# USB_OTG.net
KiCad netlist of a schematic drawn in Altium Designer
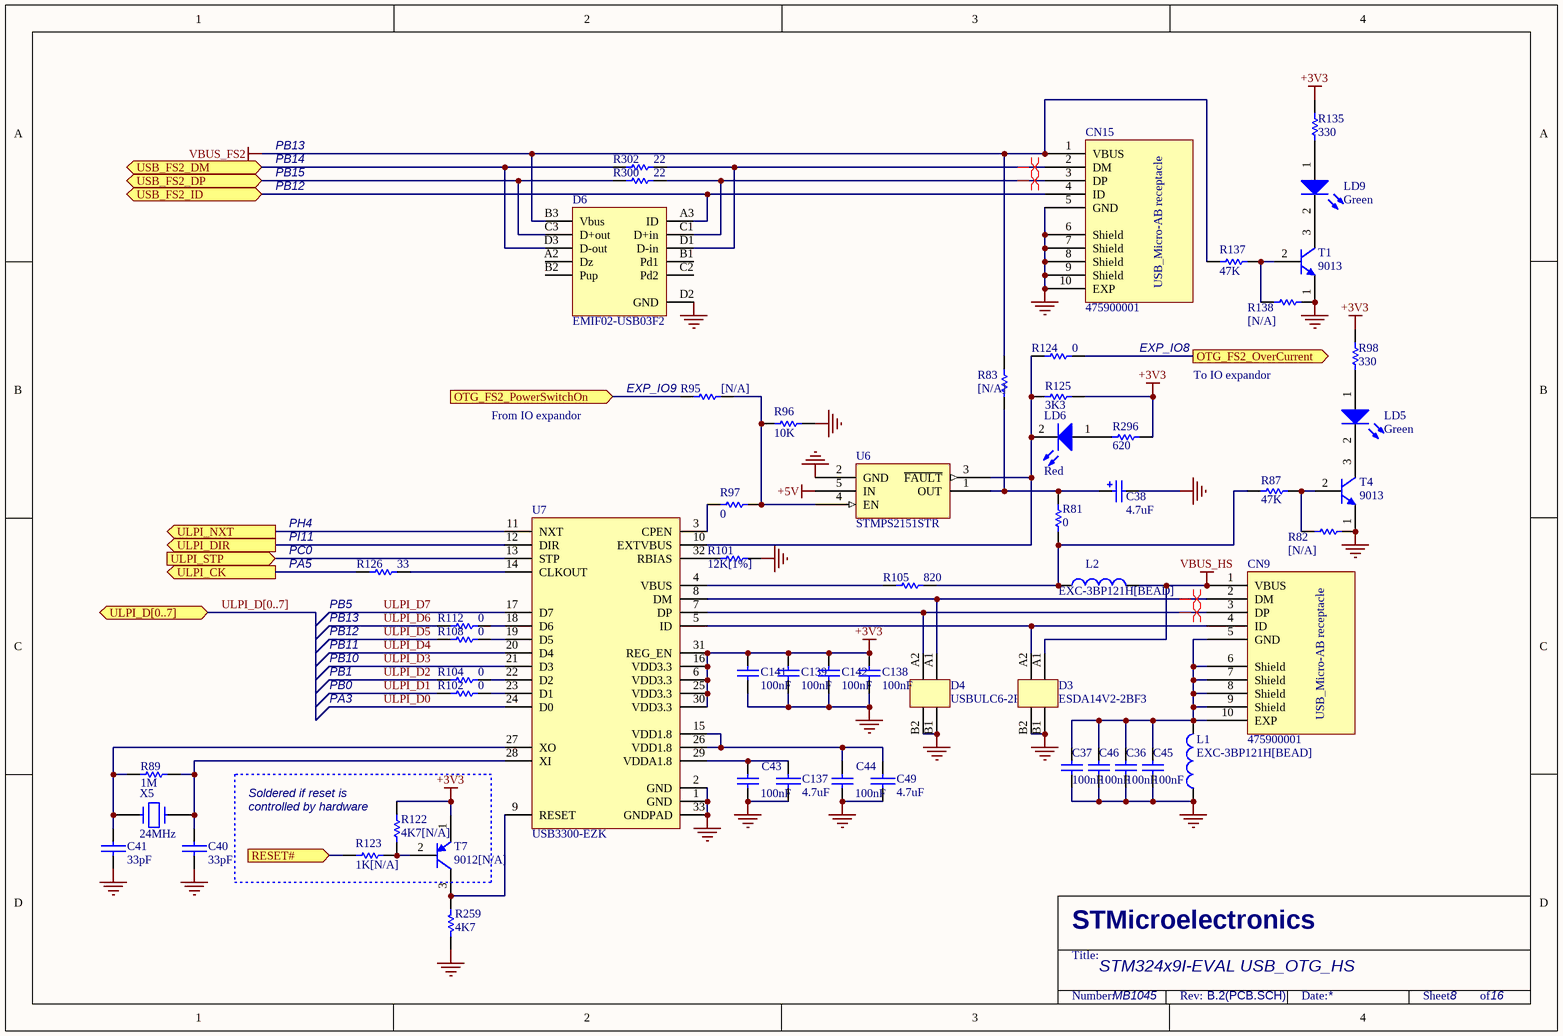
[diagram p0: USB_OTG.SchDoc]

(export (version "E")
  (design (tool "Eeschema 10.0.6"))
  (components
    (comp (ref "C36")
      (value "100nF")
      (footprint "0603C")
      (description "Capacitor")
      (fields (field (name "PUBLISHER") "Altium Limited"))
      (libsource (lib "Miscellaneous Devices") (part "Cap"))
    )
    (comp (ref "C37")
      (value "100nF")
      (footprint "0603C")
      (description "Capacitor")
      (fields (field (name "PUBLISHER") "Altium Limited"))
      (libsource (lib "Miscellaneous Devices") (part "Cap"))
    )
    (comp (ref "C38")
      (value "4.7uF")
      (footprint "TAN-A")
      (description "Polarized Capacitor (Radial)")
      (fields (field (name "PUBLISHER") "Altium Limited"))
      (libsource (lib "Miscellaneous Devices") (part "Cap Pol1"))
    )
    (comp (ref "C40")
      (value "33pF")
      (footprint "0603C")
      (description "Capacitor")
      (libsource (lib "") (part "CAP_1"))
    )
    (comp (ref "C41")
      (value "33pF")
      (footprint "0603C")
      (description "Capacitor")
      (libsource (lib "") (part "CAP_1"))
    )
    (comp (ref "C43")
      (value "100nF")
      (footprint "0603C")
      (description "Capacitor")
      (fields (field (name "PUBLISHER") "Altium Limited"))
      (libsource (lib "Miscellaneous Devices") (part "Cap"))
    )
    (comp (ref "C44")
      (value "100nF")
      (footprint "0603C")
      (description "Capacitor")
      (fields (field (name "PUBLISHER") "Altium Limited"))
      (libsource (lib "Miscellaneous Devices") (part "Cap"))
    )
    (comp (ref "C45")
      (value "100nF")
      (footprint "0603C")
      (description "Capacitor")
      (fields (field (name "PUBLISHER") "Altium Limited"))
      (libsource (lib "Miscellaneous Devices") (part "Cap"))
    )
    (comp (ref "C46")
      (value "100nF")
      (footprint "0603C")
      (description "Capacitor")
      (fields (field (name "PUBLISHER") "Altium Limited"))
      (libsource (lib "Miscellaneous Devices") (part "Cap"))
    )
    (comp (ref "C49")
      (value "4.7uF")
      (footprint "TAN-A")
      (description "Capacitor")
      (libsource (lib "*") (part "CAP"))
    )
    (comp (ref "C137")
      (value "4.7uF")
      (footprint "TAN-A")
      (description "Capacitor")
      (libsource (lib "*") (part "CAP"))
    )
    (comp (ref "C138")
      (value "100nF")
      (footprint "0603C")
      (description "Capacitor")
      (fields (field (name "PUBLISHER") "Altium Limited"))
      (libsource (lib "Miscellaneous Devices") (part "Cap"))
    )
    (comp (ref "C139")
      (value "100nF")
      (footprint "0603C")
      (description "Capacitor")
      (fields (field (name "PUBLISHER") "Altium Limited"))
      (libsource (lib "Miscellaneous Devices") (part "Cap"))
    )
    (comp (ref "C141")
      (value "100nF")
      (footprint "0603C")
      (description "Capacitor")
      (fields (field (name "PUBLISHER") "Altium Limited"))
      (libsource (lib "Miscellaneous Devices") (part "Cap"))
    )
    (comp (ref "C142")
      (value "100nF")
      (footprint "0603C")
      (description "Capacitor")
      (fields (field (name "PUBLISHER") "Altium Limited"))
      (libsource (lib "Miscellaneous Devices") (part "Cap"))
    )
    (comp (ref "CN9")
      (value "475900001")
      (footprint "MOLEX_47590001")
      (libsource (lib "mb1045") (part "475900001"))
    )
    (comp (ref "CN15")
      (value "475900001")
      (footprint "MOLEX_47590001")
      (libsource (lib "mb1045") (part "475900001"))
    )
    (comp (ref "D3")
      (value "ESDA14V2-2BF3")
      (footprint "BGA4_0R4_0R8X0R8")
      (libsource (lib "MB786") (part "ESDA14V2-2BF3"))
    )
    (comp (ref "D4")
      (value "USBULC6-2F3")
      (footprint "BGA4_0R4_1X1")
      (libsource (lib "MB786") (part "USBULC6-2F3"))
    )
    (comp (ref "D6")
      (value "EMIF02-USB03F2")
      (footprint "BGA11_0R5_1R57X2R07")
      (libsource (lib "mb1045") (part "EMIF02-USB03F2"))
    )
    (comp (ref "L1")
      (value "EXC-3BP121H[BEAD]")
      (footprint "0603L")
      (description "Inductor")
      (fields (field (name "PUBLISHER") "Altium Limited"))
      (libsource (lib "Miscellaneous Devices") (part "Inductor"))
    )
    (comp (ref "L2")
      (value "EXC-3BP121H[BEAD]")
      (footprint "0603L")
      (description "Inductor")
      (fields (field (name "PUBLISHER") "Altium Limited"))
      (libsource (lib "Miscellaneous Devices") (part "Inductor"))
    )
    (comp (ref "LD5")
      (value "Green")
      (footprint "0603D")
      (description "Typical RED, GREEN, YELLOW, AMBER GaAs LED")
      (fields (field (name "PUBLISHER") "Altium Limited"))
      (libsource (lib "Miscellaneous Devices") (part "LED2"))
    )
    (comp (ref "LD6")
      (value "Red")
      (footprint "0603D")
      (description "Typical RED, GREEN, YELLOW, AMBER GaAs LED")
      (fields (field (name "PUBLISHER") "Altium Limited"))
      (libsource (lib "Miscellaneous Devices") (part "LED2"))
    )
    (comp (ref "LD9")
      (value "Green")
      (footprint "0603D")
      (description "Typical RED, GREEN, YELLOW, AMBER GaAs LED")
      (fields (field (name "PUBLISHER") "Altium Limited"))
      (libsource (lib "Miscellaneous Devices") (part "LED2"))
    )
    (comp (ref "R81")
      (value "0")
      (footprint "0603R")
      (description "Resistor")
      (fields (field (name "PUBLISHER") "Altium Limited"))
      (libsource (lib "Miscellaneous Devices") (part "Res1"))
    )
    (comp (ref "R82")
      (value "[N/A]")
      (footprint "0603R")
      (description "Resistor")
      (fields (field (name "PUBLISHER") "Altium Limited"))
      (libsource (lib "Miscellaneous Devices") (part "res1"))
    )
    (comp (ref "R83")
      (value "[N/A]")
      (footprint "0603R")
      (description "Resistor")
      (fields (field (name "PUBLISHER") "Altium Limited"))
      (libsource (lib "Miscellaneous Devices") (part "Res1"))
    )
    (comp (ref "R87")
      (value "47K")
      (footprint "0603R")
      (description "Resistor")
      (fields (field (name "PUBLISHER") "Altium Limited"))
      (libsource (lib "Miscellaneous Devices") (part "res1"))
    )
    (comp (ref "R89")
      (value "1M")
      (footprint "0603R")
      (description "Resistor")
      (fields (field (name "PUBLISHER") "Altium Limited"))
      (libsource (lib "Miscellaneous Devices") (part "Res1"))
    )
    (comp (ref "R95")
      (value "[N/A]")
      (footprint "0603R")
      (description "Resistor")
      (fields (field (name "PUBLISHER") "Altium Limited"))
      (libsource (lib "Miscellaneous Devices") (part "Res1"))
    )
    (comp (ref "R96")
      (value "10K")
      (footprint "0603R")
      (description "Resistor")
      (fields (field (name "PUBLISHER") "Altium Limited"))
      (libsource (lib "Miscellaneous Devices") (part "res1"))
    )
    (comp (ref "R97")
      (value "0")
      (footprint "0603R")
      (description "Resistor")
      (fields (field (name "PUBLISHER") "Altium Limited"))
      (libsource (lib "Miscellaneous Devices") (part "Res1"))
    )
    (comp (ref "R98")
      (value "330")
      (footprint "0603R")
      (description "Resistor")
      (fields (field (name "PUBLISHER") "Altium Limited"))
      (libsource (lib "Miscellaneous Devices") (part "res1"))
    )
    (comp (ref "R101")
      (value "12K[1%]")
      (footprint "0603R")
      (description "Resistor")
      (fields (field (name "PUBLISHER") "Altium Limited"))
      (libsource (lib "Miscellaneous Devices") (part "Res1"))
    )
    (comp (ref "R102")
      (value "0")
      (footprint "0603R")
      (description "Resistor")
      (fields (field (name "PUBLISHER") "Altium Limited"))
      (libsource (lib "Miscellaneous Devices") (part "Res1"))
    )
    (comp (ref "R104")
      (value "0")
      (footprint "0603R")
      (description "Resistor")
      (fields (field (name "PUBLISHER") "Altium Limited"))
      (libsource (lib "Miscellaneous Devices") (part "Res1"))
    )
    (comp (ref "R105")
      (value "820")
      (footprint "0603R")
      (description "Resistor")
      (fields (field (name "PUBLISHER") "Altium Limited"))
      (libsource (lib "Miscellaneous Devices") (part "res1"))
    )
    (comp (ref "R108")
      (value "0")
      (footprint "0603R")
      (description "Resistor")
      (fields (field (name "PUBLISHER") "Altium Limited"))
      (libsource (lib "Miscellaneous Devices") (part "Res1"))
    )
    (comp (ref "R112")
      (value "0")
      (footprint "0603R")
      (description "Resistor")
      (fields (field (name "PUBLISHER") "Altium Limited"))
      (libsource (lib "Miscellaneous Devices") (part "Res1"))
    )
    (comp (ref "R122")
      (value "4K7[N/A]")
      (footprint "0603R")
      (description "Resistor")
      (fields (field (name "PUBLISHER") "Altium Limited"))
      (libsource (lib "*") (part "Res1"))
    )
    (comp (ref "R123")
      (value "1K[N/A]")
      (footprint "0603R")
      (description "Resistor")
      (fields (field (name "PUBLISHER") "Altium Limited"))
      (libsource (lib "Miscellaneous Devices") (part "Res1"))
    )
    (comp (ref "R124")
      (value "0")
      (footprint "0603R")
      (description "Resistor")
      (fields (field (name "PUBLISHER") "Altium Limited"))
      (libsource (lib "Miscellaneous Devices") (part "Res1"))
    )
    (comp (ref "R125")
      (value "3K3")
      (footprint "0603R")
      (description "Resistor")
      (fields (field (name "PUBLISHER") "Altium Limited"))
      (libsource (lib "Miscellaneous Devices") (part "res1"))
    )
    (comp (ref "R126")
      (value "33")
      (footprint "0603R")
      (description "Resistor")
      (fields (field (name "PUBLISHER") "Altium Limited"))
      (libsource (lib "Miscellaneous Devices") (part "Res1"))
    )
    (comp (ref "R135")
      (value "330")
      (footprint "0603R")
      (description "Resistor")
      (fields (field (name "PUBLISHER") "Altium Limited"))
      (libsource (lib "Miscellaneous Devices") (part "res1"))
    )
    (comp (ref "R137")
      (value "47K")
      (footprint "0603R")
      (description "Resistor")
      (fields (field (name "PUBLISHER") "Altium Limited"))
      (libsource (lib "Miscellaneous Devices") (part "res1"))
    )
    (comp (ref "R138")
      (value "[N/A]")
      (footprint "0603R")
      (description "Resistor")
      (fields (field (name "PUBLISHER") "Altium Limited"))
      (libsource (lib "Miscellaneous Devices") (part "res1"))
    )
    (comp (ref "R259")
      (value "4K7")
      (footprint "0603R")
      (description "Resistor")
      (fields (field (name "PUBLISHER") "Altium Limited"))
      (libsource (lib "*") (part "Res1"))
    )
    (comp (ref "R296")
      (value "620")
      (footprint "0603R")
      (description "Resistor")
      (fields (field (name "PUBLISHER") "Altium Limited"))
      (libsource (lib "Miscellaneous Devices") (part "Res1"))
    )
    (comp (ref "R300")
      (value "22")
      (footprint "0603R")
      (description "Resistor")
      (fields (field (name "PUBLISHER") "Altium Limited"))
      (libsource (lib "Miscellaneous Devices") (part "Res1"))
    )
    (comp (ref "R302")
      (value "22")
      (footprint "0603R")
      (description "Resistor")
      (fields (field (name "PUBLISHER") "Altium Limited"))
      (libsource (lib "Miscellaneous Devices") (part "Res1"))
    )
    (comp (ref "T1")
      (value "9013")
      (footprint "SOT23-213")
      (description "NPN Bipolar Transistor")
      (fields (field (name "PUBLISHER") "Altium Limited"))
      (libsource (lib "mb1045") (part "NPN"))
    )
    (comp (ref "T4")
      (value "9013")
      (footprint "SOT23-213")
      (description "NPN Bipolar Transistor")
      (fields (field (name "PUBLISHER") "Altium Limited"))
      (libsource (lib "mb1045") (part "NPN"))
    )
    (comp (ref "T7")
      (value "9012[N/A]")
      (footprint "SOT23-213")
      (description "PNP Bipolar Transistor")
      (fields (field (name "PUBLISHER") "Altium Limited"))
      (libsource (lib "Miscellaneous Devices") (part "PNP"))
    )
    (comp (ref "U6")
      (value "STMPS2151STR")
      (footprint "SOT23-5")
      (libsource (lib "mb1045") (part "STMPS2141STR"))
    )
    (comp (ref "U7")
      (value "USB3300-EZK")
      (footprint "QFN32_0R5_5X5")
      (libsource (lib "MB1000_1") (part "USB3300-EZK"))
    )
    (comp (ref "X5")
      (value "24MHz")
      (footprint "XTAL1")
      (description "Crystal")
      (libsource (lib "*") (part "CRYSTAL"))
    )
  )
  (nets
    (net (code "1") (name "+3V3") (class "Default")
      (node (ref "C138") (pin "1") (pinfunction "1_1") (pintype "passive"))
      (node (ref "C139") (pin "1") (pinfunction "1_1") (pintype "passive"))
      (node (ref "C141") (pin "1") (pinfunction "1_1") (pintype "passive"))
      (node (ref "C142") (pin "1") (pinfunction "1_1") (pintype "passive"))
      (node (ref "R122") (pin "1") (pinfunction "1_1") (pintype "passive"))
      (node (ref "R125") (pin "1") (pinfunction "1_1") (pintype "passive"))
      (node (ref "R135") (pin "2") (pinfunction "2_2") (pintype "passive"))
      (node (ref "R296") (pin "2") (pinfunction "2_2") (pintype "passive"))
      (node (ref "R98") (pin "2") (pinfunction "2_2") (pintype "passive"))
      (node (ref "T7") (pin "1") (pinfunction "E_1") (pintype "passive"))
      (node (ref "U7") (pin "16") (pinfunction "VDD3.3_16") (pintype "passive"))
      (node (ref "U7") (pin "25") (pinfunction "VDD3.3_25") (pintype "passive"))
      (node (ref "U7") (pin "30") (pinfunction "VDD3.3_30") (pintype "passive"))
      (node (ref "U7") (pin "31") (pinfunction "REG_EN_31") (pintype "passive"))
      (node (ref "U7") (pin "6") (pinfunction "VDD3.3_6") (pintype "passive"))
    )
    (net (code "2") (name "+5V") (class "Default")
      (node (ref "U6") (pin "5") (pinfunction "IN_5") (pintype "passive"))
    )
    (net (code "3") (name "/OTG_FS2_OverCurrent") (class "Default")
      (node (ref "R124") (pin "1") (pinfunction "1_1") (pintype "passive"))
    )
    (net (code "4") (name "/OTG_FS2_PowerSwitchOn") (class "Default")
      (node (ref "R95") (pin "2") (pinfunction "2_2") (pintype "passive"))
    )
    (net (code "5") (name "/RESET#") (class "Default")
      (node (ref "R123") (pin "2") (pinfunction "2_2") (pintype "passive"))
    )
    (net (code "6") (name "/ULPI_CK") (class "Default")
      (node (ref "R126") (pin "2") (pinfunction "2_2") (pintype "passive"))
    )
    (net (code "7") (name "/ULPI_D0") (class "Default")
      (node (ref "U7") (pin "24") (pinfunction "D0_24") (pintype "passive"))
    )
    (net (code "8") (name "/ULPI_D1") (class "Default")
      (node (ref "R102") (pin "2") (pinfunction "2_2") (pintype "passive"))
    )
    (net (code "9") (name "/ULPI_D2") (class "Default")
      (node (ref "R104") (pin "2") (pinfunction "2_2") (pintype "passive"))
    )
    (net (code "10") (name "/ULPI_D3") (class "Default")
      (node (ref "U7") (pin "21") (pinfunction "D3_21") (pintype "passive"))
    )
    (net (code "11") (name "/ULPI_D4") (class "Default")
      (node (ref "U7") (pin "20") (pinfunction "D4_20") (pintype "passive"))
    )
    (net (code "12") (name "/ULPI_D5") (class "Default")
      (node (ref "R108") (pin "2") (pinfunction "2_2") (pintype "passive"))
    )
    (net (code "13") (name "/ULPI_D6") (class "Default")
      (node (ref "R112") (pin "2") (pinfunction "2_2") (pintype "passive"))
    )
    (net (code "14") (name "/ULPI_D7") (class "Default")
      (node (ref "U7") (pin "17") (pinfunction "D7_17") (pintype "passive"))
    )
    (net (code "15") (name "/ULPI_DIR") (class "Default")
      (node (ref "U7") (pin "12") (pinfunction "DIR_12") (pintype "passive"))
    )
    (net (code "17") (name "/ULPI_NXT") (class "Default")
      (node (ref "U7") (pin "11") (pinfunction "NXT_11") (pintype "passive"))
    )
    (net (code "18") (name "/ULPI_STP") (class "Default")
      (node (ref "U7") (pin "13") (pinfunction "STP_13") (pintype "passive"))
    )
    (net (code "19") (name "/USB_FS2_DM") (class "Default")
      (node (ref "D6") (pin "D3") (pinfunction "D-out_D3") (pintype "passive"))
      (node (ref "R302") (pin "2") (pinfunction "2_2") (pintype "passive"))
    )
    (net (code "20") (name "/USB_FS2_DP") (class "Default")
      (node (ref "D6") (pin "C3") (pinfunction "D+out_C3") (pintype "passive"))
      (node (ref "R300") (pin "2") (pinfunction "2_2") (pintype "passive"))
    )
    (net (code "21") (name "/USB_FS2_ID") (class "Default")
      (node (ref "CN15") (pin "4") (pinfunction "ID_4") (pintype "passive"))
      (node (ref "D6") (pin "A3") (pinfunction "ID_A3") (pintype "passive"))
    )
    (net (code "22") (name "GND") (class "Default")
      (node (ref "C137") (pin "2") (pinfunction "2_2") (pintype "passive"))
      (node (ref "C138") (pin "2") (pinfunction "2_2") (pintype "passive"))
      (node (ref "C139") (pin "2") (pinfunction "2_2") (pintype "passive"))
      (node (ref "C141") (pin "2") (pinfunction "2_2") (pintype "passive"))
      (node (ref "C142") (pin "2") (pinfunction "2_2") (pintype "passive"))
      (node (ref "C36") (pin "2") (pinfunction "2_2") (pintype "passive"))
      (node (ref "C37") (pin "2") (pinfunction "2_2") (pintype "passive"))
      (node (ref "C38") (pin "2") (pinfunction "2_2") (pintype "passive"))
      (node (ref "C40") (pin "2") (pinfunction "2_2") (pintype "passive"))
      (node (ref "C41") (pin "2") (pinfunction "2_2") (pintype "passive"))
      (node (ref "C43") (pin "2") (pinfunction "2_2") (pintype "passive"))
      (node (ref "C44") (pin "2") (pinfunction "2_2") (pintype "passive"))
      (node (ref "C45") (pin "2") (pinfunction "2_2") (pintype "passive"))
      (node (ref "C46") (pin "2") (pinfunction "2_2") (pintype "passive"))
      (node (ref "C49") (pin "2") (pinfunction "2_2") (pintype "passive"))
      (node (ref "CN15") (pin "10") (pinfunction "EXP_10") (pintype "passive"))
      (node (ref "CN15") (pin "5") (pinfunction "GND_5") (pintype "passive"))
      (node (ref "CN15") (pin "6") (pinfunction "Shield_6") (pintype "passive"))
      (node (ref "CN15") (pin "7") (pinfunction "Shield_7") (pintype "passive"))
      (node (ref "CN15") (pin "8") (pinfunction "Shield_8") (pintype "passive"))
      (node (ref "CN15") (pin "9") (pinfunction "Shield_9") (pintype "passive"))
      (node (ref "D3") (pin "B1") (pintype "passive"))
      (node (ref "D3") (pin "B2") (pintype "passive"))
      (node (ref "D4") (pin "B1") (pintype "passive"))
      (node (ref "D4") (pin "B2") (pintype "passive"))
      (node (ref "D6") (pin "D2") (pinfunction "GND_D2") (pintype "passive"))
      (node (ref "L1") (pin "1") (pinfunction "1_1") (pintype "passive"))
      (node (ref "R101") (pin "1") (pinfunction "1_1") (pintype "passive"))
      (node (ref "R138") (pin "1") (pinfunction "1_1") (pintype "passive"))
      (node (ref "R259") (pin "1") (pinfunction "1_1") (pintype "passive"))
      (node (ref "R82") (pin "1") (pinfunction "1_1") (pintype "passive"))
      (node (ref "R96") (pin "1") (pinfunction "1_1") (pintype "passive"))
      (node (ref "T1") (pin "1") (pinfunction "E_1") (pintype "passive"))
      (node (ref "T4") (pin "1") (pinfunction "E_1") (pintype "passive"))
      (node (ref "U6") (pin "2") (pinfunction "GND_2") (pintype "passive"))
      (node (ref "U7") (pin "1") (pinfunction "GND_1") (pintype "passive"))
      (node (ref "U7") (pin "2") (pinfunction "GND_2") (pintype "passive"))
      (node (ref "U7") (pin "33") (pinfunction "GNDPAD_33") (pintype "passive"))
    )
    (net (code "23") (name "Net-(C44-Pad1)") (class "Default")
      (node (ref "C44") (pin "1") (pinfunction "1_1") (pintype "passive"))
      (node (ref "C49") (pin "1") (pinfunction "1_1") (pintype "passive"))
      (node (ref "U7") (pin "15") (pinfunction "VDD1.8_15") (pintype "passive"))
      (node (ref "U7") (pin "26") (pinfunction "VDD1.8_26") (pintype "passive"))
    )
    (net (code "24") (name "Net-(CN9-DM)") (class "Default")
      (node (ref "CN9") (pin "2") (pinfunction "DM_2") (pintype "passive"))
      (node (ref "D4") (pin "A1") (pintype "passive"))
      (node (ref "U7") (pin "8") (pinfunction "DM_8") (pintype "passive"))
    )
    (net (code "25") (name "Net-(CN9-DP)") (class "Default")
      (node (ref "CN9") (pin "3") (pinfunction "DP_3") (pintype "passive"))
      (node (ref "D4") (pin "A2") (pintype "passive"))
      (node (ref "U7") (pin "7") (pinfunction "DP_7") (pintype "passive"))
    )
    (net (code "26") (name "Net-(CN9-EXP)") (class "Default")
      (node (ref "C36") (pin "1") (pinfunction "1_1") (pintype "passive"))
      (node (ref "C37") (pin "1") (pinfunction "1_1") (pintype "passive"))
      (node (ref "C45") (pin "1") (pinfunction "1_1") (pintype "passive"))
      (node (ref "C46") (pin "1") (pinfunction "1_1") (pintype "passive"))
      (node (ref "CN9") (pin "10") (pinfunction "EXP_10") (pintype "passive"))
      (node (ref "CN9") (pin "5") (pinfunction "GND_5") (pintype "passive"))
      (node (ref "CN9") (pin "6") (pinfunction "Shield_6") (pintype "passive"))
      (node (ref "CN9") (pin "7") (pinfunction "Shield_7") (pintype "passive"))
      (node (ref "CN9") (pin "8") (pinfunction "Shield_8") (pintype "passive"))
      (node (ref "CN9") (pin "9") (pinfunction "Shield_9") (pintype "passive"))
      (node (ref "L1") (pin "2") (pinfunction "2_2") (pintype "passive"))
    )
    (net (code "27") (name "Net-(CN9-ID)") (class "Default")
      (node (ref "CN9") (pin "4") (pinfunction "ID_4") (pintype "passive"))
      (node (ref "D3") (pin "A2") (pintype "passive"))
      (node (ref "U7") (pin "5") (pinfunction "ID_5") (pintype "passive"))
    )
    (net (code "28") (name "Net-(CN15-DM)") (class "Default")
      (node (ref "CN15") (pin "2") (pinfunction "DM_2") (pintype "passive"))
      (node (ref "D6") (pin "D1") (pinfunction "D-in_D1") (pintype "passive"))
      (node (ref "R302") (pin "1") (pinfunction "1_1") (pintype "passive"))
    )
    (net (code "29") (name "Net-(CN15-DP)") (class "Default")
      (node (ref "CN15") (pin "3") (pinfunction "DP_3") (pintype "passive"))
      (node (ref "D6") (pin "C1") (pinfunction "D+in_C1") (pintype "passive"))
      (node (ref "R300") (pin "1") (pinfunction "1_1") (pintype "passive"))
    )
    (net (code "30") (name "Net-(L2-Pad1)") (class "Default")
      (node (ref "L2") (pin "1") (pinfunction "1_1") (pintype "passive"))
      (node (ref "R105") (pin "2") (pinfunction "2_2") (pintype "passive"))
      (node (ref "R81") (pin "2") (pinfunction "2_2") (pintype "passive"))
      (node (ref "R87") (pin "2") (pinfunction "2_2") (pintype "passive"))
    )
    (net (code "31") (name "Net-(LD5-A)") (class "Default")
      (node (ref "LD5") (pin "1") (pinfunction "A_1") (pintype "passive"))
      (node (ref "R98") (pin "1") (pinfunction "1_1") (pintype "passive"))
    )
    (net (code "32") (name "Net-(LD5-K)") (class "Default")
      (node (ref "LD5") (pin "2") (pinfunction "K_2") (pintype "passive"))
      (node (ref "T4") (pin "3") (pinfunction "C_3") (pintype "passive"))
    )
    (net (code "33") (name "Net-(LD6-A)") (class "Default")
      (node (ref "LD6") (pin "1") (pinfunction "A_1") (pintype "passive"))
      (node (ref "R296") (pin "1") (pinfunction "1_1") (pintype "passive"))
    )
    (net (code "34") (name "Net-(LD6-K)") (class "Default")
      (node (ref "LD6") (pin "2") (pinfunction "K_2") (pintype "passive"))
      (node (ref "R124") (pin "2") (pinfunction "2_2") (pintype "passive"))
      (node (ref "R125") (pin "2") (pinfunction "2_2") (pintype "passive"))
      (node (ref "U6") (pin "3") (pinfunction "~{FAULT}_3") (pintype "output"))
      (node (ref "U7") (pin "10") (pinfunction "EXTVBUS_10") (pintype "passive"))
    )
    (net (code "35") (name "Net-(LD9-A)") (class "Default")
      (node (ref "LD9") (pin "1") (pinfunction "A_1") (pintype "passive"))
      (node (ref "R135") (pin "1") (pinfunction "1_1") (pintype "passive"))
    )
    (net (code "36") (name "Net-(LD9-K)") (class "Default")
      (node (ref "LD9") (pin "2") (pinfunction "K_2") (pintype "passive"))
      (node (ref "T1") (pin "3") (pinfunction "C_3") (pintype "passive"))
    )
    (net (code "37") (name "Net-(T1-B)") (class "Default")
      (node (ref "R137") (pin "2") (pinfunction "2_2") (pintype "passive"))
      (node (ref "R138") (pin "2") (pinfunction "2_2") (pintype "passive"))
      (node (ref "T1") (pin "2") (pinfunction "B_2") (pintype "passive"))
    )
    (net (code "38") (name "Net-(T4-B)") (class "Default")
      (node (ref "R82") (pin "2") (pinfunction "2_2") (pintype "passive"))
      (node (ref "R87") (pin "1") (pinfunction "1_1") (pintype "passive"))
      (node (ref "T4") (pin "2") (pinfunction "B_2") (pintype "passive"))
    )
    (net (code "39") (name "Net-(T7-B)") (class "Default")
      (node (ref "R122") (pin "2") (pinfunction "2_2") (pintype "passive"))
      (node (ref "R123") (pin "1") (pinfunction "1_1") (pintype "passive"))
      (node (ref "T7") (pin "2") (pinfunction "B_2") (pintype "passive"))
    )
    (net (code "40") (name "Net-(T7-C)") (class "Default")
      (node (ref "R259") (pin "2") (pinfunction "2_2") (pintype "passive"))
      (node (ref "T7") (pin "3") (pinfunction "C_3") (pintype "passive"))
      (node (ref "U7") (pin "9") (pinfunction "RESET_9") (pintype "passive"))
    )
    (net (code "41") (name "Net-(U6-EN)") (class "Default")
      (node (ref "R95") (pin "1") (pinfunction "1_1") (pintype "passive"))
      (node (ref "R96") (pin "2") (pinfunction "2_2") (pintype "passive"))
      (node (ref "R97") (pin "2") (pinfunction "2_2") (pintype "passive"))
      (node (ref "U6") (pin "4") (pinfunction "EN_4") (pintype "input"))
    )
    (net (code "42") (name "Net-(U6-OUT)") (class "Default")
      (node (ref "C38") (pin "1") (pinfunction "1_1") (pintype "passive"))
      (node (ref "R81") (pin "1") (pinfunction "1_1") (pintype "passive"))
      (node (ref "R83") (pin "2") (pinfunction "2_2") (pintype "passive"))
      (node (ref "U6") (pin "1") (pinfunction "OUT_1") (pintype "passive"))
    )
    (net (code "43") (name "Net-(U7-CLKOUT)") (class "Default")
      (node (ref "R126") (pin "1") (pinfunction "1_1") (pintype "passive"))
      (node (ref "U7") (pin "14") (pinfunction "CLKOUT_14") (pintype "passive"))
    )
    (net (code "44") (name "Net-(U7-CPEN)") (class "Default")
      (node (ref "R97") (pin "1") (pinfunction "1_1") (pintype "passive"))
      (node (ref "U7") (pin "3") (pinfunction "CPEN_3") (pintype "passive"))
    )
    (net (code "45") (name "Net-(U7-D1)") (class "Default")
      (node (ref "R102") (pin "1") (pinfunction "1_1") (pintype "passive"))
      (node (ref "U7") (pin "23") (pinfunction "D1_23") (pintype "passive"))
    )
    (net (code "46") (name "Net-(U7-D2)") (class "Default")
      (node (ref "R104") (pin "1") (pinfunction "1_1") (pintype "passive"))
      (node (ref "U7") (pin "22") (pinfunction "D2_22") (pintype "passive"))
    )
    (net (code "47") (name "Net-(U7-D5)") (class "Default")
      (node (ref "R108") (pin "1") (pinfunction "1_1") (pintype "passive"))
      (node (ref "U7") (pin "19") (pinfunction "D5_19") (pintype "passive"))
    )
    (net (code "48") (name "Net-(U7-D6)") (class "Default")
      (node (ref "R112") (pin "1") (pinfunction "1_1") (pintype "passive"))
      (node (ref "U7") (pin "18") (pinfunction "D6_18") (pintype "passive"))
    )
    (net (code "49") (name "Net-(U7-RBIAS)") (class "Default")
      (node (ref "R101") (pin "2") (pinfunction "2_2") (pintype "passive"))
      (node (ref "U7") (pin "32") (pinfunction "RBIAS_32") (pintype "passive"))
    )
    (net (code "50") (name "Net-(U7-VBUS)") (class "Default")
      (node (ref "R105") (pin "1") (pinfunction "1_1") (pintype "passive"))
      (node (ref "U7") (pin "4") (pinfunction "VBUS_4") (pintype "passive"))
    )
    (net (code "51") (name "Net-(U7-VDDA1.8)") (class "Default")
      (node (ref "C137") (pin "1") (pinfunction "1_1") (pintype "passive"))
      (node (ref "C43") (pin "1") (pinfunction "1_1") (pintype "passive"))
      (node (ref "U7") (pin "29") (pinfunction "VDDA1.8_29") (pintype "passive"))
    )
    (net (code "52") (name "Net-(U7-XI)") (class "Default")
      (node (ref "C40") (pin "1") (pinfunction "1_1") (pintype "passive"))
      (node (ref "R89") (pin "2") (pinfunction "2_2") (pintype "passive"))
      (node (ref "U7") (pin "28") (pinfunction "XI_28") (pintype "passive"))
      (node (ref "X5") (pin "1") (pinfunction "1_1") (pintype "passive"))
    )
    (net (code "53") (name "Net-(U7-XO)") (class "Default")
      (node (ref "C41") (pin "1") (pinfunction "1_1") (pintype "passive"))
      (node (ref "R89") (pin "1") (pinfunction "1_1") (pintype "passive"))
      (node (ref "U7") (pin "27") (pinfunction "XO_27") (pintype "passive"))
      (node (ref "X5") (pin "2") (pinfunction "2_2") (pintype "passive"))
    )
    (net (code "54") (name "VBUS_FS2") (class "Default")
      (node (ref "CN15") (pin "1") (pinfunction "VBUS_1") (pintype "passive"))
      (node (ref "D6") (pin "B3") (pinfunction "Vbus_B3") (pintype "passive"))
      (node (ref "R137") (pin "1") (pinfunction "1_1") (pintype "passive"))
      (node (ref "R83") (pin "1") (pinfunction "1_1") (pintype "passive"))
    )
    (net (code "55") (name "VBUS_HS") (class "Default")
      (node (ref "CN9") (pin "1") (pinfunction "VBUS_1") (pintype "passive"))
      (node (ref "D3") (pin "A1") (pintype "passive"))
      (node (ref "L2") (pin "2") (pinfunction "2_2") (pintype "passive"))
    )
    (net (code "56") (name "unconnected-(D6-Dz-PadA2)") (class "Default")
      (node (ref "D6") (pin "A2") (pinfunction "Dz_A2") (pintype "passive"))
    )
    (net (code "57") (name "unconnected-(D6-Pd1-PadB1)") (class "Default")
      (node (ref "D6") (pin "B1") (pinfunction "Pd1_B1") (pintype "passive"))
    )
    (net (code "58") (name "unconnected-(D6-Pd2-PadC2)") (class "Default")
      (node (ref "D6") (pin "C2") (pinfunction "Pd2_C2") (pintype "passive"))
    )
    (net (code "59") (name "unconnected-(D6-Pup-PadB2)") (class "Default")
      (node (ref "D6") (pin "B2") (pinfunction "Pup_B2") (pintype "passive"))
    )
  )
)
